# DueShield.net
KiCad netlist of a schematic drawn in EAGLE
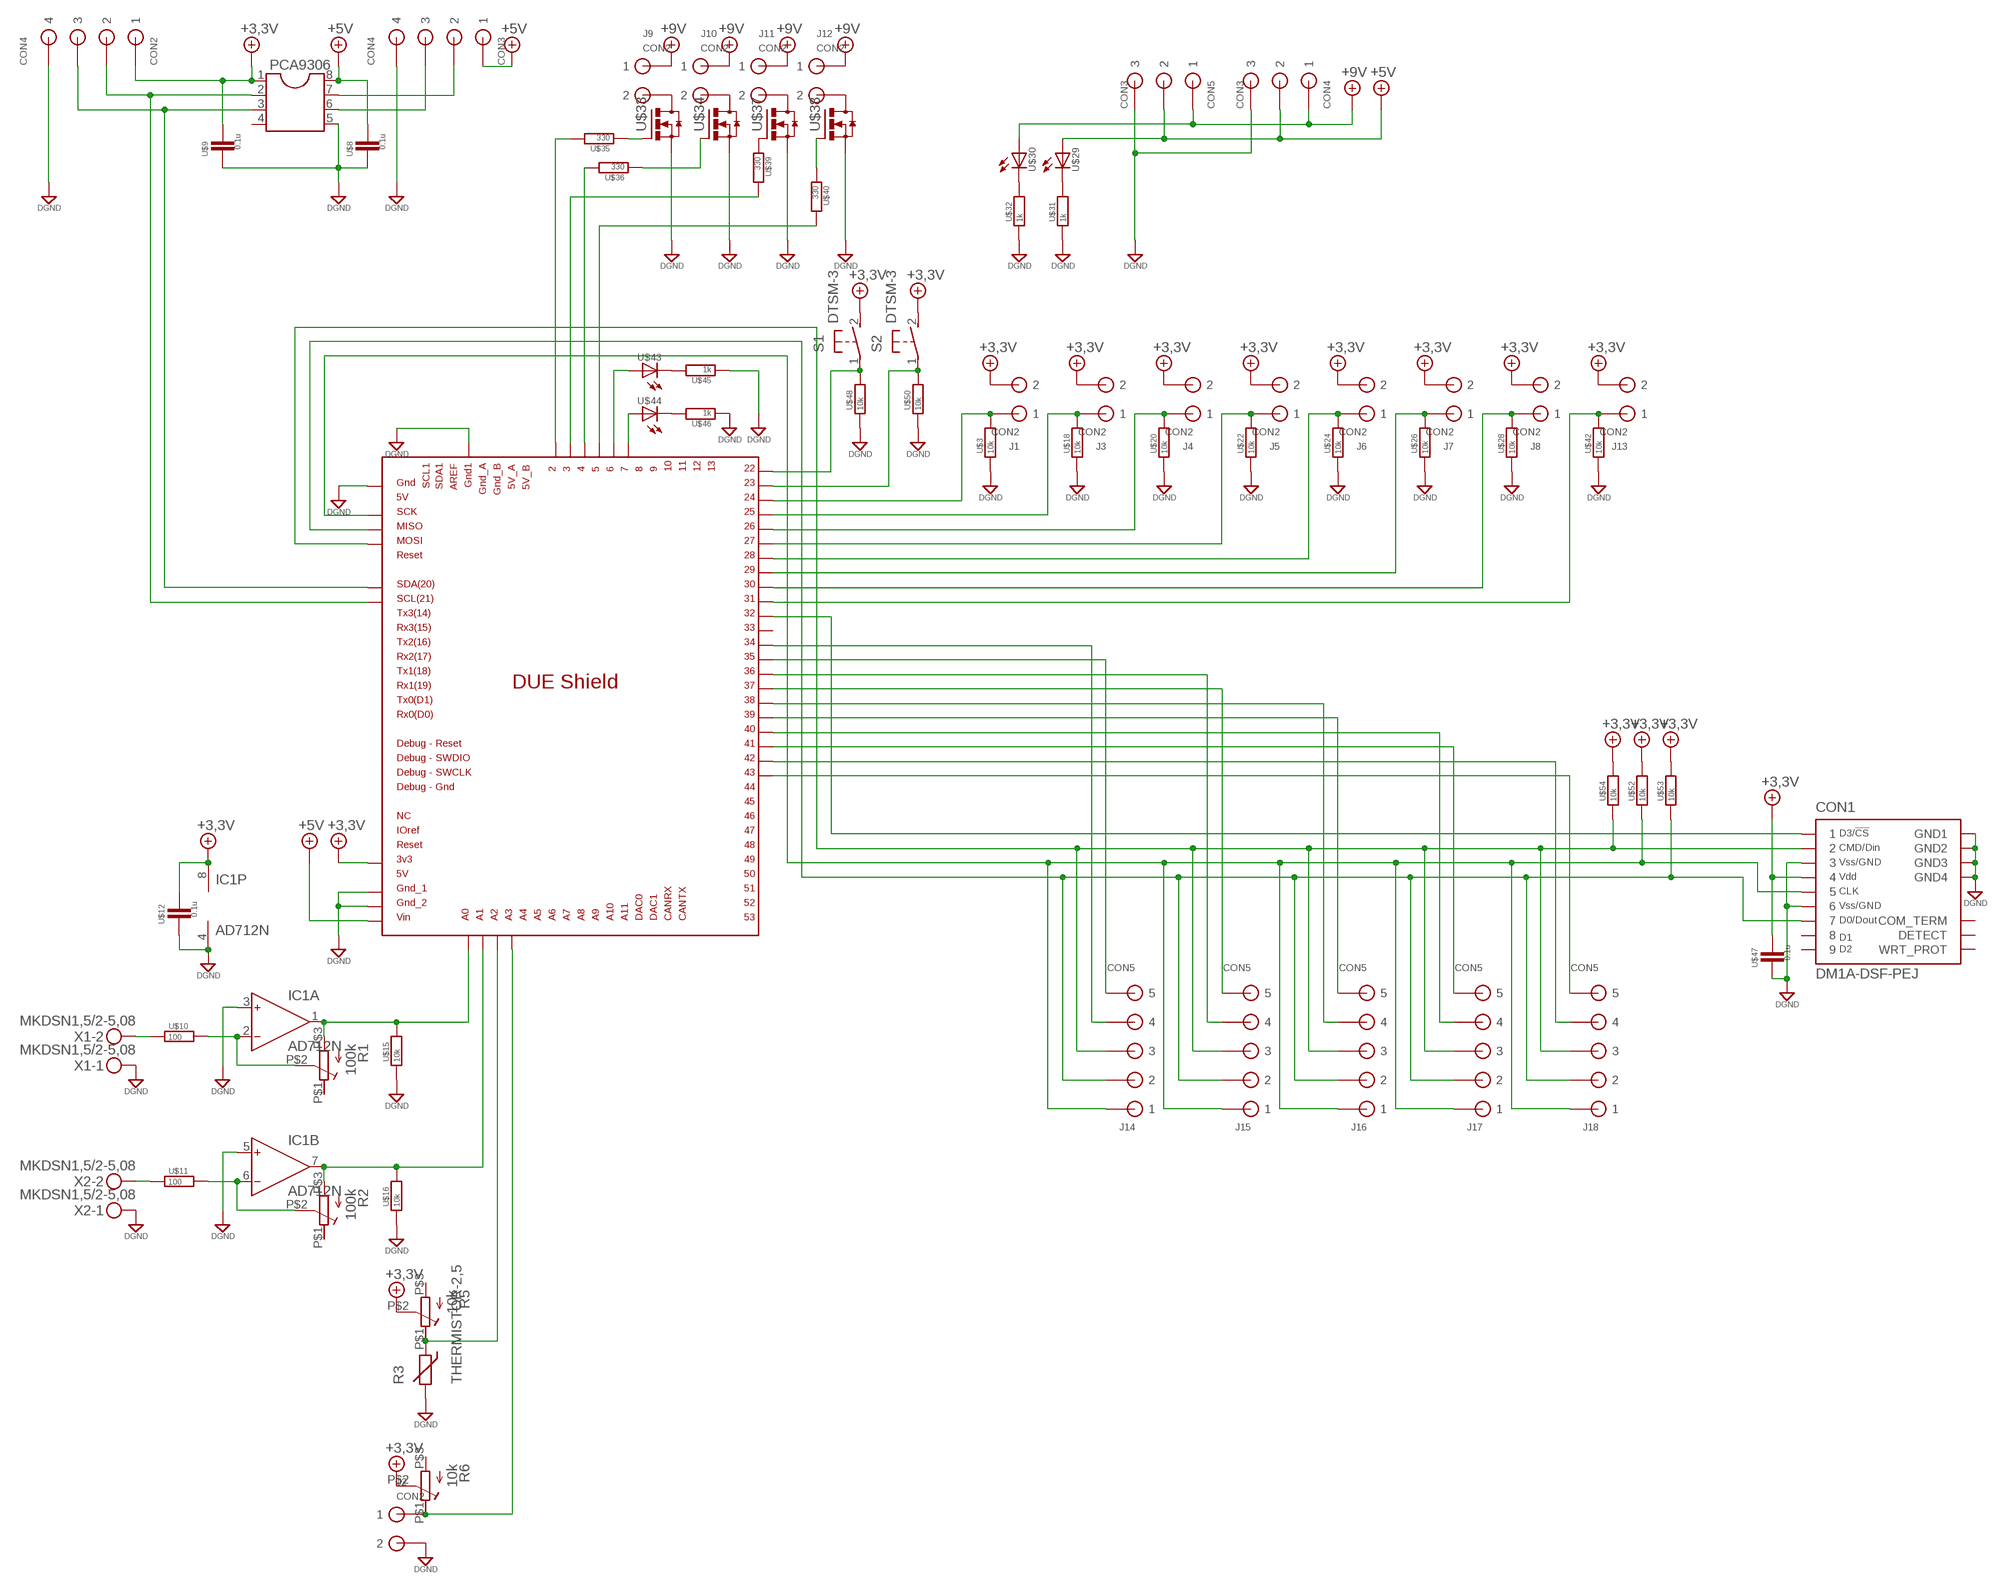
[diagram p0: schematic, sheet 1]

(export (version "E")
  (design (tool "Eeschema 10.0.6"))
  (components
    (comp (ref "CON1")
      (value "DM1A-DSF-PEJ")
      (footprint "eagle-import:DM1A-DSF-PEJ")
      (libsource (lib "eagle-import") (part "DM1A-DSF-PEJ"))
    )
    (comp (ref "CON2")
      (value "CON4")
      (footprint "eagle-import:CON4")
      (libsource (lib "eagle-import") (part "CON4"))
    )
    (comp (ref "CON3")
      (value "CON4")
      (footprint "eagle-import:CON4")
      (libsource (lib "eagle-import") (part "CON4"))
    )
    (comp (ref "CON4")
      (value "CON3")
      (footprint "eagle-import:CON3")
      (libsource (lib "eagle-import") (part "CON3"))
    )
    (comp (ref "CON5")
      (value "CON3")
      (footprint "eagle-import:CON3")
      (libsource (lib "eagle-import") (part "CON3"))
    )
    (comp (ref "IC1")
      (value "AD712N")
      (footprint "eagle-import:DIL08")
      (fields (field (name "MF") "ALTERA CORPORATION") (field (name "MPN") "AD712JNZ"))
      (libsource (lib "eagle-import") (part "AD712N"))
    )
    (comp (ref "J1")
      (value "CON2")
      (footprint "eagle-import:CON2")
      (libsource (lib "eagle-import") (part "CON2"))
    )
    (comp (ref "J2")
      (value "CON2")
      (footprint "eagle-import:CON2")
      (libsource (lib "eagle-import") (part "CON2"))
    )
    (comp (ref "J3")
      (value "CON2")
      (footprint "eagle-import:CON2")
      (libsource (lib "eagle-import") (part "CON2"))
    )
    (comp (ref "J4")
      (value "CON2")
      (footprint "eagle-import:CON2")
      (libsource (lib "eagle-import") (part "CON2"))
    )
    (comp (ref "J5")
      (value "CON2")
      (footprint "eagle-import:CON2")
      (libsource (lib "eagle-import") (part "CON2"))
    )
    (comp (ref "J6")
      (value "CON2")
      (footprint "eagle-import:CON2")
      (libsource (lib "eagle-import") (part "CON2"))
    )
    (comp (ref "J7")
      (value "CON2")
      (footprint "eagle-import:CON2")
      (libsource (lib "eagle-import") (part "CON2"))
    )
    (comp (ref "J8")
      (value "CON2")
      (footprint "eagle-import:CON2")
      (libsource (lib "eagle-import") (part "CON2"))
    )
    (comp (ref "J9")
      (value "CON2")
      (footprint "eagle-import:CON2")
      (libsource (lib "eagle-import") (part "CON2"))
    )
    (comp (ref "J10")
      (value "CON2")
      (footprint "eagle-import:CON2")
      (libsource (lib "eagle-import") (part "CON2"))
    )
    (comp (ref "J11")
      (value "CON2")
      (footprint "eagle-import:CON2")
      (libsource (lib "eagle-import") (part "CON2"))
    )
    (comp (ref "J12")
      (value "CON2")
      (footprint "eagle-import:CON2")
      (libsource (lib "eagle-import") (part "CON2"))
    )
    (comp (ref "J13")
      (value "CON2")
      (footprint "eagle-import:CON2")
      (libsource (lib "eagle-import") (part "CON2"))
    )
    (comp (ref "J14")
      (value "CON5")
      (footprint "eagle-import:CON5")
      (libsource (lib "eagle-import") (part "CON5"))
    )
    (comp (ref "J15")
      (value "CON5")
      (footprint "eagle-import:CON5")
      (libsource (lib "eagle-import") (part "CON5"))
    )
    (comp (ref "J16")
      (value "CON5")
      (footprint "eagle-import:CON5")
      (libsource (lib "eagle-import") (part "CON5"))
    )
    (comp (ref "J17")
      (value "CON5")
      (footprint "eagle-import:CON5")
      (libsource (lib "eagle-import") (part "CON5"))
    )
    (comp (ref "J18")
      (value "CON5")
      (footprint "eagle-import:CON5")
      (libsource (lib "eagle-import") (part "CON5"))
    )
    (comp (ref "PCA9306")
      (value "DIL8")
      (footprint "eagle-import:DIL08")
      (libsource (lib "eagle-import") (part "DIL8"))
    )
    (comp (ref "R1")
      (value "100k")
      (footprint "eagle-import:GF063PB")
      (libsource (lib "eagle-import") (part "抵抗(可変)"))
    )
    (comp (ref "R2")
      (value "100k")
      (footprint "eagle-import:GF063PB")
      (libsource (lib "eagle-import") (part "抵抗(可変)"))
    )
    (comp (ref "R3")
      (value "THERMISTOR-2,5")
      (footprint "eagle-import:RS-2,5")
      (libsource (lib "eagle-import") (part "THERMISTOR-2,5"))
    )
    (comp (ref "R5")
      (value "10k")
      (footprint "eagle-import:GF063PB")
      (libsource (lib "eagle-import") (part "抵抗(可変)"))
    )
    (comp (ref "R6")
      (value "10k")
      (footprint "eagle-import:GF063PB")
      (libsource (lib "eagle-import") (part "抵抗(可変)"))
    )
    (comp (ref "S1")
      (value "DTSM-3")
      (footprint "eagle-import:DTSM-3")
      (libsource (lib "eagle-import") (part "DTSM-3"))
    )
    (comp (ref "S2")
      (value "DTSM-3")
      (footprint "eagle-import:DTSM-3")
      (libsource (lib "eagle-import") (part "DTSM-3"))
    )
    (comp (ref "U$1")
      (value "DUE(3DPRINTER)")
      (footprint "eagle-import:DUE(3DPRITNER)")
      (libsource (lib "eagle-import") (part "DUE(3DPRINTER)"))
    )
    (comp (ref "U$3")
      (value "10k")
      (footprint "eagle-import:0805")
      (libsource (lib "eagle-import") (part "抵抗0805"))
    )
    (comp (ref "U$8")
      (value "0.1u")
      (footprint "eagle-import:0805")
      (libsource (lib "eagle-import") (part "コンデンサ0805"))
    )
    (comp (ref "U$9")
      (value "0.1u")
      (footprint "eagle-import:0805")
      (libsource (lib "eagle-import") (part "コンデンサ0805"))
    )
    (comp (ref "U$10")
      (value "100")
      (footprint "eagle-import:0805")
      (libsource (lib "eagle-import") (part "抵抗0805"))
    )
    (comp (ref "U$11")
      (value "100")
      (footprint "eagle-import:0805")
      (libsource (lib "eagle-import") (part "抵抗0805"))
    )
    (comp (ref "U$12")
      (value "0.1u")
      (footprint "eagle-import:0805")
      (libsource (lib "eagle-import") (part "コンデンサ0805"))
    )
    (comp (ref "U$15")
      (value "10k")
      (footprint "eagle-import:0805")
      (libsource (lib "eagle-import") (part "抵抗0805"))
    )
    (comp (ref "U$16")
      (value "10k")
      (footprint "eagle-import:0805")
      (libsource (lib "eagle-import") (part "抵抗0805"))
    )
    (comp (ref "U$18")
      (value "10k")
      (footprint "eagle-import:0805")
      (libsource (lib "eagle-import") (part "抵抗0805"))
    )
    (comp (ref "U$20")
      (value "10k")
      (footprint "eagle-import:0805")
      (libsource (lib "eagle-import") (part "抵抗0805"))
    )
    (comp (ref "U$22")
      (value "10k")
      (footprint "eagle-import:0805")
      (libsource (lib "eagle-import") (part "抵抗0805"))
    )
    (comp (ref "U$24")
      (value "10k")
      (footprint "eagle-import:0805")
      (libsource (lib "eagle-import") (part "抵抗0805"))
    )
    (comp (ref "U$26")
      (value "10k")
      (footprint "eagle-import:0805")
      (libsource (lib "eagle-import") (part "抵抗0805"))
    )
    (comp (ref "U$28")
      (value "10k")
      (footprint "eagle-import:0805")
      (libsource (lib "eagle-import") (part "抵抗0805"))
    )
    (comp (ref "U$29")
      (value "LED(砲弾型)3")
      (footprint "eagle-import:LED3MM")
      (libsource (lib "eagle-import") (part "LED(砲弾型)3"))
    )
    (comp (ref "U$30")
      (value "LED(砲弾型)3")
      (footprint "eagle-import:LED3MM")
      (libsource (lib "eagle-import") (part "LED(砲弾型)3"))
    )
    (comp (ref "U$31")
      (value "1k")
      (footprint "eagle-import:0805")
      (libsource (lib "eagle-import") (part "抵抗0805"))
    )
    (comp (ref "U$32")
      (value "1k")
      (footprint "eagle-import:0805")
      (libsource (lib "eagle-import") (part "抵抗0805"))
    )
    (comp (ref "U$33")
      (value "TO-252(MOS-FET_N)")
      (footprint "eagle-import:TO-252")
      (libsource (lib "eagle-import") (part "TO-252(MOS-FET_N)"))
    )
    (comp (ref "U$34")
      (value "TO-252(MOS-FET_N)")
      (footprint "eagle-import:TO-252")
      (libsource (lib "eagle-import") (part "TO-252(MOS-FET_N)"))
    )
    (comp (ref "U$35")
      (value "330")
      (footprint "eagle-import:0805")
      (libsource (lib "eagle-import") (part "抵抗0805"))
    )
    (comp (ref "U$36")
      (value "330")
      (footprint "eagle-import:0805")
      (libsource (lib "eagle-import") (part "抵抗0805"))
    )
    (comp (ref "U$37")
      (value "TO-252(MOS-FET_N)")
      (footprint "eagle-import:TO-252")
      (libsource (lib "eagle-import") (part "TO-252(MOS-FET_N)"))
    )
    (comp (ref "U$38")
      (value "TO-252(MOS-FET_N)")
      (footprint "eagle-import:TO-252")
      (libsource (lib "eagle-import") (part "TO-252(MOS-FET_N)"))
    )
    (comp (ref "U$39")
      (value "330")
      (footprint "eagle-import:0805")
      (libsource (lib "eagle-import") (part "抵抗0805"))
    )
    (comp (ref "U$40")
      (value "330")
      (footprint "eagle-import:0805")
      (libsource (lib "eagle-import") (part "抵抗0805"))
    )
    (comp (ref "U$42")
      (value "10k")
      (footprint "eagle-import:0805")
      (libsource (lib "eagle-import") (part "抵抗0805"))
    )
    (comp (ref "U$43")
      (value "LED(砲弾型)3")
      (footprint "eagle-import:LED3MM")
      (libsource (lib "eagle-import") (part "LED(砲弾型)3"))
    )
    (comp (ref "U$44")
      (value "LED(砲弾型)3")
      (footprint "eagle-import:LED3MM")
      (libsource (lib "eagle-import") (part "LED(砲弾型)3"))
    )
    (comp (ref "U$45")
      (value "1k")
      (footprint "eagle-import:0805")
      (libsource (lib "eagle-import") (part "抵抗0805"))
    )
    (comp (ref "U$46")
      (value "1k")
      (footprint "eagle-import:0805")
      (libsource (lib "eagle-import") (part "抵抗0805"))
    )
    (comp (ref "U$47")
      (value "0.1u")
      (footprint "eagle-import:0805")
      (libsource (lib "eagle-import") (part "コンデンサ0805"))
    )
    (comp (ref "U$48")
      (value "10k")
      (footprint "eagle-import:0805")
      (libsource (lib "eagle-import") (part "抵抗0805"))
    )
    (comp (ref "U$50")
      (value "10k")
      (footprint "eagle-import:0805")
      (libsource (lib "eagle-import") (part "抵抗0805"))
    )
    (comp (ref "U$52")
      (value "10k")
      (footprint "eagle-import:0805")
      (libsource (lib "eagle-import") (part "抵抗0805"))
    )
    (comp (ref "U$53")
      (value "10k")
      (footprint "eagle-import:0805")
      (libsource (lib "eagle-import") (part "抵抗0805"))
    )
    (comp (ref "U$54")
      (value "10k")
      (footprint "eagle-import:0805")
      (libsource (lib "eagle-import") (part "抵抗0805"))
    )
    (comp (ref "X1")
      (value "MKDSN1,5/2-5,08")
      (footprint "eagle-import:MKDSN1,5_2-5,08")
      (libsource (lib "eagle-import") (part "MKDSN1,5/2-5,08"))
    )
    (comp (ref "X2")
      (value "MKDSN1,5/2-5,08")
      (footprint "eagle-import:MKDSN1,5_2-5,08")
      (libsource (lib "eagle-import") (part "MKDSN1,5/2-5,08"))
    )
  )
  (nets
    (net (code "1") (name "+3.3V") (class "Default")
      (node (ref "CON1") (pin "4") (pinfunction "4_4") (pintype "power_in"))
      (node (ref "CON2") (pin "P$1") (pinfunction "1_P$1") (pintype "bidirectional"))
      (node (ref "IC1") (pin "8") (pinfunction "V+_8") (pintype "power_in"))
      (node (ref "J1") (pin "P$2") (pinfunction "2_P$2") (pintype "bidirectional"))
      (node (ref "J13") (pin "P$2") (pinfunction "2_P$2") (pintype "bidirectional"))
      (node (ref "J3") (pin "P$2") (pinfunction "2_P$2") (pintype "bidirectional"))
      (node (ref "J4") (pin "P$2") (pinfunction "2_P$2") (pintype "bidirectional"))
      (node (ref "J5") (pin "P$2") (pinfunction "2_P$2") (pintype "bidirectional"))
      (node (ref "J6") (pin "P$2") (pinfunction "2_P$2") (pintype "bidirectional"))
      (node (ref "J7") (pin "P$2") (pinfunction "2_P$2") (pintype "bidirectional"))
      (node (ref "J8") (pin "P$2") (pinfunction "2_P$2") (pintype "bidirectional"))
      (node (ref "PCA9306") (pin "1") (pinfunction "1_1") (pintype "passive"))
      (node (ref "R5") (pin "P$2") (pinfunction "S_P$2") (pintype "passive"))
      (node (ref "R6") (pin "P$2") (pinfunction "S_P$2") (pintype "passive"))
      (node (ref "S1") (pin "2") (pinfunction "2_2") (pintype "passive"))
      (node (ref "S2") (pin "2") (pinfunction "2_2") (pintype "passive"))
      (node (ref "U$1") (pin "3V3") (pinfunction "3V3_3V3") (pintype "bidirectional"))
      (node (ref "U$12") (pin "1") (pinfunction "1_1") (pintype "passive"))
      (node (ref "U$47") (pin "1") (pinfunction "1_1") (pintype "passive"))
      (node (ref "U$52") (pin "2") (pinfunction "2_2") (pintype "passive"))
      (node (ref "U$53") (pin "2") (pinfunction "2_2") (pintype "passive"))
      (node (ref "U$54") (pin "2") (pinfunction "2_2") (pintype "passive"))
      (node (ref "U$9") (pin "1") (pinfunction "1_1") (pintype "passive"))
    )
    (net (code "2") (name "+5V") (class "Default")
      (node (ref "CON3") (pin "P$1") (pinfunction "1_P$1") (pintype "bidirectional"))
      (node (ref "CON4") (pin "P$2") (pinfunction "2_P$2") (pintype "bidirectional"))
      (node (ref "CON5") (pin "P$2") (pinfunction "2_P$2") (pintype "bidirectional"))
      (node (ref "PCA9306") (pin "8") (pinfunction "8_8") (pintype "passive"))
      (node (ref "U$1") (pin "VIN") (pinfunction "VIN_VIN") (pintype "bidirectional"))
      (node (ref "U$29") (pin "A") (pinfunction "A_A") (pintype "passive"))
      (node (ref "U$8") (pin "1") (pinfunction "1_1") (pintype "passive"))
    )
    (net (code "3") (name "+9V") (class "Default")
      (node (ref "CON4") (pin "P$1") (pinfunction "1_P$1") (pintype "bidirectional"))
      (node (ref "CON5") (pin "P$1") (pinfunction "1_P$1") (pintype "bidirectional"))
      (node (ref "J10") (pin "P$1") (pinfunction "1_P$1") (pintype "bidirectional"))
      (node (ref "J11") (pin "P$1") (pinfunction "1_P$1") (pintype "bidirectional"))
      (node (ref "J12") (pin "P$1") (pinfunction "1_P$1") (pintype "bidirectional"))
      (node (ref "J9") (pin "P$1") (pinfunction "1_P$1") (pintype "bidirectional"))
      (node (ref "U$30") (pin "A") (pinfunction "A_A") (pintype "passive"))
    )
    (net (code "4") (name "DGND") (class "Default")
      (node (ref "CON1") (pin "3") (pinfunction "3_3") (pintype "power_in"))
      (node (ref "CON1") (pin "6") (pinfunction "6_6") (pintype "power_in"))
      (node (ref "CON1") (pin "GND1") (pinfunction "GND1_GND1") (pintype "power_in"))
      (node (ref "CON1") (pin "GND2") (pinfunction "GND2_GND2") (pintype "power_in"))
      (node (ref "CON1") (pin "GND3") (pinfunction "GND3_GND3") (pintype "power_in"))
      (node (ref "CON1") (pin "GND4") (pinfunction "GND4_GND4") (pintype "power_in"))
      (node (ref "CON2") (pin "P$4") (pinfunction "4_P$4") (pintype "bidirectional"))
      (node (ref "CON3") (pin "P$4") (pinfunction "4_P$4") (pintype "bidirectional"))
      (node (ref "CON4") (pin "P$3") (pinfunction "3_P$3") (pintype "bidirectional"))
      (node (ref "CON5") (pin "P$3") (pinfunction "3_P$3") (pintype "bidirectional"))
      (node (ref "IC1") (pin "3") (pinfunction "IN+_3") (pintype "input"))
      (node (ref "IC1") (pin "4") (pinfunction "V-_4") (pintype "power_in"))
      (node (ref "IC1") (pin "5") (pinfunction "IN+_5") (pintype "input"))
      (node (ref "J2") (pin "P$2") (pinfunction "2_P$2") (pintype "bidirectional"))
      (node (ref "PCA9306") (pin "5") (pinfunction "5_5") (pintype "passive"))
      (node (ref "R3") (pin "2") (pinfunction "2_2") (pintype "passive"))
      (node (ref "U$1") (pin "5V_ICSP") (pinfunction "5V_ICSP_5V_ICSP") (pintype "bidirectional"))
      (node (ref "U$1") (pin "GND1") (pinfunction "GND1_GND1") (pintype "bidirectional"))
      (node (ref "U$1") (pin "GND_1") (pinfunction "GND_1_GND_1") (pintype "bidirectional"))
      (node (ref "U$1") (pin "GND_2") (pinfunction "GND_2_GND_2") (pintype "bidirectional"))
      (node (ref "U$12") (pin "2") (pinfunction "2_2") (pintype "passive"))
      (node (ref "U$15") (pin "1") (pinfunction "1_1") (pintype "passive"))
      (node (ref "U$16") (pin "1") (pinfunction "1_1") (pintype "passive"))
      (node (ref "U$18") (pin "1") (pinfunction "1_1") (pintype "passive"))
      (node (ref "U$20") (pin "1") (pinfunction "1_1") (pintype "passive"))
      (node (ref "U$22") (pin "1") (pinfunction "1_1") (pintype "passive"))
      (node (ref "U$24") (pin "1") (pinfunction "1_1") (pintype "passive"))
      (node (ref "U$26") (pin "1") (pinfunction "1_1") (pintype "passive"))
      (node (ref "U$28") (pin "1") (pinfunction "1_1") (pintype "passive"))
      (node (ref "U$3") (pin "1") (pinfunction "1_1") (pintype "passive"))
      (node (ref "U$31") (pin "1") (pinfunction "1_1") (pintype "passive"))
      (node (ref "U$32") (pin "1") (pinfunction "1_1") (pintype "passive"))
      (node (ref "U$33") (pin "2") (pinfunction "S_2") (pintype "passive"))
      (node (ref "U$34") (pin "2") (pinfunction "S_2") (pintype "passive"))
      (node (ref "U$37") (pin "2") (pinfunction "S_2") (pintype "passive"))
      (node (ref "U$38") (pin "2") (pinfunction "S_2") (pintype "passive"))
      (node (ref "U$42") (pin "1") (pinfunction "1_1") (pintype "passive"))
      (node (ref "U$45") (pin "1") (pinfunction "1_1") (pintype "passive"))
      (node (ref "U$46") (pin "1") (pinfunction "1_1") (pintype "passive"))
      (node (ref "U$47") (pin "2") (pinfunction "2_2") (pintype "passive"))
      (node (ref "U$48") (pin "1") (pinfunction "1_1") (pintype "passive"))
      (node (ref "U$50") (pin "1") (pinfunction "1_1") (pintype "passive"))
      (node (ref "U$8") (pin "2") (pinfunction "2_2") (pintype "passive"))
      (node (ref "U$9") (pin "2") (pinfunction "2_2") (pintype "passive"))
      (node (ref "X1") (pin "1") (pinfunction "KL_1") (pintype "passive"))
      (node (ref "X2") (pin "1") (pinfunction "KL_1") (pintype "passive"))
    )
    (net (code "5") (name "Net-(CON1-Pad1)") (class "Default")
      (node (ref "CON1") (pin "1") (pinfunction "1_1") (pintype "bidirectional"))
      (node (ref "U$1") (pin "32") (pinfunction "32_32") (pintype "bidirectional"))
    )
    (net (code "6") (name "Net-(CON2-2)") (class "Default")
      (node (ref "CON2") (pin "P$2") (pinfunction "2_P$2") (pintype "bidirectional"))
      (node (ref "PCA9306") (pin "2") (pinfunction "2_2") (pintype "passive"))
      (node (ref "U$1") (pin "SCL") (pinfunction "SCL_SCL") (pintype "bidirectional"))
    )
    (net (code "7") (name "Net-(CON2-3)") (class "Default")
      (node (ref "CON2") (pin "P$3") (pinfunction "3_P$3") (pintype "bidirectional"))
      (node (ref "PCA9306") (pin "3") (pinfunction "3_3") (pintype "passive"))
      (node (ref "U$1") (pin "SDA") (pinfunction "SDA_SDA") (pintype "bidirectional"))
    )
    (net (code "8") (name "Net-(CON3-2)") (class "Default")
      (node (ref "CON3") (pin "P$2") (pinfunction "2_P$2") (pintype "bidirectional"))
      (node (ref "PCA9306") (pin "7") (pinfunction "7_7") (pintype "passive"))
    )
    (net (code "9") (name "Net-(CON3-3)") (class "Default")
      (node (ref "CON3") (pin "P$3") (pinfunction "3_P$3") (pintype "bidirectional"))
      (node (ref "PCA9306") (pin "6") (pinfunction "6_6") (pintype "passive"))
    )
    (net (code "10") (name "Net-(IC1A-IN-)") (class "Default")
      (node (ref "IC1") (pin "2") (pinfunction "IN-_2") (pintype "input"))
      (node (ref "R1") (pin "P$2") (pinfunction "S_P$2") (pintype "passive"))
      (node (ref "U$10") (pin "2") (pinfunction "2_2") (pintype "passive"))
    )
    (net (code "11") (name "Net-(IC1A-OUT)") (class "Default")
      (node (ref "IC1") (pin "1") (pinfunction "OUT_1") (pintype "output"))
      (node (ref "R1") (pin "P$3") (pinfunction "A_P$3") (pintype "passive"))
      (node (ref "U$1") (pin "A0") (pinfunction "A0_A0") (pintype "bidirectional"))
      (node (ref "U$15") (pin "2") (pinfunction "2_2") (pintype "passive"))
    )
    (net (code "12") (name "Net-(IC1B-IN-)") (class "Default")
      (node (ref "IC1") (pin "6") (pinfunction "IN-_6") (pintype "input"))
      (node (ref "R2") (pin "P$2") (pinfunction "S_P$2") (pintype "passive"))
      (node (ref "U$11") (pin "2") (pinfunction "2_2") (pintype "passive"))
    )
    (net (code "13") (name "Net-(IC1B-OUT)") (class "Default")
      (node (ref "IC1") (pin "7") (pinfunction "OUT_7") (pintype "output"))
      (node (ref "R2") (pin "P$3") (pinfunction "A_P$3") (pintype "passive"))
      (node (ref "U$1") (pin "A1") (pinfunction "A1_A1") (pintype "bidirectional"))
      (node (ref "U$16") (pin "2") (pinfunction "2_2") (pintype "passive"))
    )
    (net (code "14") (name "Net-(J1-1)") (class "Default")
      (node (ref "J1") (pin "P$1") (pinfunction "1_P$1") (pintype "bidirectional"))
      (node (ref "U$1") (pin "24") (pinfunction "24_24") (pintype "bidirectional"))
      (node (ref "U$3") (pin "2") (pinfunction "2_2") (pintype "passive"))
    )
    (net (code "15") (name "Net-(J2-1)") (class "Default")
      (node (ref "J2") (pin "P$1") (pinfunction "1_P$1") (pintype "bidirectional"))
      (node (ref "R6") (pin "P$1") (pinfunction "E_P$1") (pintype "passive"))
      (node (ref "U$1") (pin "A3") (pinfunction "A3_A3") (pintype "bidirectional"))
    )
    (net (code "16") (name "Net-(J3-1)") (class "Default")
      (node (ref "J3") (pin "P$1") (pinfunction "1_P$1") (pintype "bidirectional"))
      (node (ref "U$1") (pin "25") (pinfunction "25_25") (pintype "bidirectional"))
      (node (ref "U$18") (pin "2") (pinfunction "2_2") (pintype "passive"))
    )
    (net (code "17") (name "Net-(J4-1)") (class "Default")
      (node (ref "J4") (pin "P$1") (pinfunction "1_P$1") (pintype "bidirectional"))
      (node (ref "U$1") (pin "26") (pinfunction "26_26") (pintype "bidirectional"))
      (node (ref "U$20") (pin "2") (pinfunction "2_2") (pintype "passive"))
    )
    (net (code "18") (name "Net-(J5-1)") (class "Default")
      (node (ref "J5") (pin "P$1") (pinfunction "1_P$1") (pintype "bidirectional"))
      (node (ref "U$1") (pin "27") (pinfunction "27_27") (pintype "bidirectional"))
      (node (ref "U$22") (pin "2") (pinfunction "2_2") (pintype "passive"))
    )
    (net (code "19") (name "Net-(J6-1)") (class "Default")
      (node (ref "J6") (pin "P$1") (pinfunction "1_P$1") (pintype "bidirectional"))
      (node (ref "U$1") (pin "28") (pinfunction "28_28") (pintype "bidirectional"))
      (node (ref "U$24") (pin "2") (pinfunction "2_2") (pintype "passive"))
    )
    (net (code "20") (name "Net-(J7-1)") (class "Default")
      (node (ref "J7") (pin "P$1") (pinfunction "1_P$1") (pintype "bidirectional"))
      (node (ref "U$1") (pin "29") (pinfunction "29_29") (pintype "bidirectional"))
      (node (ref "U$26") (pin "2") (pinfunction "2_2") (pintype "passive"))
    )
    (net (code "21") (name "Net-(J8-1)") (class "Default")
      (node (ref "J8") (pin "P$1") (pinfunction "1_P$1") (pintype "bidirectional"))
      (node (ref "U$1") (pin "30") (pinfunction "30_30") (pintype "bidirectional"))
      (node (ref "U$28") (pin "2") (pinfunction "2_2") (pintype "passive"))
    )
    (net (code "22") (name "Net-(J9-2)") (class "Default")
      (node (ref "J9") (pin "P$2") (pinfunction "2_P$2") (pintype "bidirectional"))
      (node (ref "U$33") (pin "3") (pinfunction "D_3") (pintype "passive"))
    )
    (net (code "23") (name "Net-(J10-2)") (class "Default")
      (node (ref "J10") (pin "P$2") (pinfunction "2_P$2") (pintype "bidirectional"))
      (node (ref "U$34") (pin "3") (pinfunction "D_3") (pintype "passive"))
    )
    (net (code "24") (name "Net-(J11-2)") (class "Default")
      (node (ref "J11") (pin "P$2") (pinfunction "2_P$2") (pintype "bidirectional"))
      (node (ref "U$37") (pin "3") (pinfunction "D_3") (pintype "passive"))
    )
    (net (code "25") (name "Net-(J12-2)") (class "Default")
      (node (ref "J12") (pin "P$2") (pinfunction "2_P$2") (pintype "bidirectional"))
      (node (ref "U$38") (pin "3") (pinfunction "D_3") (pintype "passive"))
    )
    (net (code "26") (name "Net-(J13-1)") (class "Default")
      (node (ref "J13") (pin "P$1") (pinfunction "1_P$1") (pintype "bidirectional"))
      (node (ref "U$1") (pin "31") (pinfunction "31_31") (pintype "bidirectional"))
      (node (ref "U$42") (pin "2") (pinfunction "2_2") (pintype "passive"))
    )
    (net (code "27") (name "Net-(J14-1)") (class "Default")
      (node (ref "CON1") (pin "5") (pinfunction "5_5") (pintype "input"))
      (node (ref "J14") (pin "P$1") (pinfunction "1_P$1") (pintype "bidirectional"))
      (node (ref "J15") (pin "P$1") (pinfunction "1_P$1") (pintype "bidirectional"))
      (node (ref "J16") (pin "P$1") (pinfunction "1_P$1") (pintype "bidirectional"))
      (node (ref "J17") (pin "P$1") (pinfunction "1_P$1") (pintype "bidirectional"))
      (node (ref "J18") (pin "P$1") (pinfunction "1_P$1") (pintype "bidirectional"))
      (node (ref "U$1") (pin "SCK_ICSP") (pinfunction "SCK_ICSP_SCK_ICSP") (pintype "bidirectional"))
      (node (ref "U$52") (pin "1") (pinfunction "1_1") (pintype "passive"))
    )
    (net (code "28") (name "Net-(J14-2)") (class "Default")
      (node (ref "CON1") (pin "7") (pinfunction "7_7") (pintype "bidirectional"))
      (node (ref "J14") (pin "P$2") (pinfunction "2_P$2") (pintype "bidirectional"))
      (node (ref "J15") (pin "P$2") (pinfunction "2_P$2") (pintype "bidirectional"))
      (node (ref "J16") (pin "P$2") (pinfunction "2_P$2") (pintype "bidirectional"))
      (node (ref "J17") (pin "P$2") (pinfunction "2_P$2") (pintype "bidirectional"))
      (node (ref "J18") (pin "P$2") (pinfunction "2_P$2") (pintype "bidirectional"))
      (node (ref "U$1") (pin "MISO_ICSP") (pinfunction "MISO_ICSP_MISO_ICSP") (pintype "bidirectional"))
      (node (ref "U$53") (pin "1") (pinfunction "1_1") (pintype "passive"))
    )
    (net (code "29") (name "Net-(J14-3)") (class "Default")
      (node (ref "CON1") (pin "2") (pinfunction "2_2") (pintype "input"))
      (node (ref "J14") (pin "P$3") (pinfunction "3_P$3") (pintype "bidirectional"))
      (node (ref "J15") (pin "P$3") (pinfunction "3_P$3") (pintype "bidirectional"))
      (node (ref "J16") (pin "P$3") (pinfunction "3_P$3") (pintype "bidirectional"))
      (node (ref "J17") (pin "P$3") (pinfunction "3_P$3") (pintype "bidirectional"))
      (node (ref "J18") (pin "P$3") (pinfunction "3_P$3") (pintype "bidirectional"))
      (node (ref "U$1") (pin "MOSI_ICSP") (pinfunction "MOSI_ICSP_MOSI_ICSP") (pintype "bidirectional"))
      (node (ref "U$54") (pin "1") (pinfunction "1_1") (pintype "passive"))
    )
    (net (code "30") (name "Net-(J14-4)") (class "Default")
      (node (ref "J14") (pin "P$4") (pinfunction "4_P$4") (pintype "bidirectional"))
      (node (ref "U$1") (pin "34") (pinfunction "34_34") (pintype "bidirectional"))
    )
    (net (code "31") (name "Net-(J14-5)") (class "Default")
      (node (ref "J14") (pin "P$5") (pinfunction "5_P$5") (pintype "bidirectional"))
      (node (ref "U$1") (pin "35") (pinfunction "35_35") (pintype "bidirectional"))
    )
    (net (code "32") (name "Net-(J15-4)") (class "Default")
      (node (ref "J15") (pin "P$4") (pinfunction "4_P$4") (pintype "bidirectional"))
      (node (ref "U$1") (pin "36") (pinfunction "36_36") (pintype "bidirectional"))
    )
    (net (code "33") (name "Net-(J15-5)") (class "Default")
      (node (ref "J15") (pin "P$5") (pinfunction "5_P$5") (pintype "bidirectional"))
      (node (ref "U$1") (pin "37") (pinfunction "37_37") (pintype "bidirectional"))
    )
    (net (code "34") (name "Net-(J16-4)") (class "Default")
      (node (ref "J16") (pin "P$4") (pinfunction "4_P$4") (pintype "bidirectional"))
      (node (ref "U$1") (pin "38") (pinfunction "38_38") (pintype "bidirectional"))
    )
    (net (code "35") (name "Net-(J16-5)") (class "Default")
      (node (ref "J16") (pin "P$5") (pinfunction "5_P$5") (pintype "bidirectional"))
      (node (ref "U$1") (pin "39") (pinfunction "39_39") (pintype "bidirectional"))
    )
    (net (code "36") (name "Net-(J17-4)") (class "Default")
      (node (ref "J17") (pin "P$4") (pinfunction "4_P$4") (pintype "bidirectional"))
      (node (ref "U$1") (pin "40") (pinfunction "40_40") (pintype "bidirectional"))
    )
    (net (code "37") (name "Net-(J17-5)") (class "Default")
      (node (ref "J17") (pin "P$5") (pinfunction "5_P$5") (pintype "bidirectional"))
      (node (ref "U$1") (pin "41") (pinfunction "41_41") (pintype "bidirectional"))
    )
    (net (code "38") (name "Net-(J18-4)") (class "Default")
      (node (ref "J18") (pin "P$4") (pinfunction "4_P$4") (pintype "bidirectional"))
      (node (ref "U$1") (pin "42") (pinfunction "42_42") (pintype "bidirectional"))
    )
    (net (code "39") (name "Net-(J18-5)") (class "Default")
      (node (ref "J18") (pin "P$5") (pinfunction "5_P$5") (pintype "bidirectional"))
      (node (ref "U$1") (pin "43") (pinfunction "43_43") (pintype "bidirectional"))
    )
    (net (code "40") (name "Net-(R5-E)") (class "Default")
      (node (ref "R3") (pin "1") (pinfunction "1_1") (pintype "passive"))
      (node (ref "R5") (pin "P$1") (pinfunction "E_P$1") (pintype "passive"))
      (node (ref "U$1") (pin "A2") (pinfunction "A2_A2") (pintype "bidirectional"))
    )
    (net (code "41") (name "Net-(S1-Pad1)") (class "Default")
      (node (ref "S1") (pin "1") (pinfunction "1_1") (pintype "passive"))
      (node (ref "U$1") (pin "22") (pinfunction "22_22") (pintype "bidirectional"))
      (node (ref "U$48") (pin "2") (pinfunction "2_2") (pintype "passive"))
    )
    (net (code "42") (name "Net-(S2-Pad1)") (class "Default")
      (node (ref "S2") (pin "1") (pinfunction "1_1") (pintype "passive"))
      (node (ref "U$1") (pin "23") (pinfunction "23_23") (pintype "bidirectional"))
      (node (ref "U$50") (pin "2") (pinfunction "2_2") (pintype "passive"))
    )
    (net (code "43") (name "Net-(U$1-Pad2)") (class "Default")
      (node (ref "U$1") (pin "2") (pinfunction "2_2") (pintype "bidirectional"))
      (node (ref "U$35") (pin "2") (pinfunction "2_2") (pintype "passive"))
    )
    (net (code "44") (name "Net-(U$1-Pad3)") (class "Default")
      (node (ref "U$1") (pin "3") (pinfunction "3_3") (pintype "bidirectional"))
      (node (ref "U$39") (pin "2") (pinfunction "2_2") (pintype "passive"))
    )
    (net (code "45") (name "Net-(U$1-Pad4)") (class "Default")
      (node (ref "U$1") (pin "4") (pinfunction "4_4") (pintype "bidirectional"))
      (node (ref "U$36") (pin "2") (pinfunction "2_2") (pintype "passive"))
    )
    (net (code "46") (name "Net-(U$1-Pad5)") (class "Default")
      (node (ref "U$1") (pin "5") (pinfunction "5_5") (pintype "bidirectional"))
      (node (ref "U$40") (pin "2") (pinfunction "2_2") (pintype "passive"))
    )
    (net (code "47") (name "Net-(U$1-Pad6)") (class "Default")
      (node (ref "U$1") (pin "6") (pinfunction "6_6") (pintype "bidirectional"))
      (node (ref "U$43") (pin "A") (pinfunction "A_A") (pintype "passive"))
    )
    (net (code "48") (name "Net-(U$1-Pad7)") (class "Default")
      (node (ref "U$1") (pin "7") (pinfunction "7_7") (pintype "bidirectional"))
      (node (ref "U$44") (pin "A") (pinfunction "A_A") (pintype "passive"))
    )
    (net (code "49") (name "Net-(U$29-PadK)") (class "Default")
      (node (ref "U$29") (pin "K") (pinfunction "K_K") (pintype "passive"))
      (node (ref "U$31") (pin "2") (pinfunction "2_2") (pintype "passive"))
    )
    (net (code "50") (name "Net-(U$30-PadK)") (class "Default")
      (node (ref "U$30") (pin "K") (pinfunction "K_K") (pintype "passive"))
      (node (ref "U$32") (pin "2") (pinfunction "2_2") (pintype "passive"))
    )
    (net (code "51") (name "Net-(U$33-G)") (class "Default")
      (node (ref "U$33") (pin "1") (pinfunction "G_1") (pintype "passive"))
      (node (ref "U$35") (pin "1") (pinfunction "1_1") (pintype "passive"))
    )
    (net (code "52") (name "Net-(U$34-G)") (class "Default")
      (node (ref "U$34") (pin "1") (pinfunction "G_1") (pintype "passive"))
      (node (ref "U$36") (pin "1") (pinfunction "1_1") (pintype "passive"))
    )
    (net (code "53") (name "Net-(U$37-G)") (class "Default")
      (node (ref "U$37") (pin "1") (pinfunction "G_1") (pintype "passive"))
      (node (ref "U$39") (pin "1") (pinfunction "1_1") (pintype "passive"))
    )
    (net (code "54") (name "Net-(U$38-G)") (class "Default")
      (node (ref "U$38") (pin "1") (pinfunction "G_1") (pintype "passive"))
      (node (ref "U$40") (pin "1") (pinfunction "1_1") (pintype "passive"))
    )
    (net (code "55") (name "Net-(U$43-PadK)") (class "Default")
      (node (ref "U$43") (pin "K") (pinfunction "K_K") (pintype "passive"))
      (node (ref "U$45") (pin "2") (pinfunction "2_2") (pintype "passive"))
    )
    (net (code "56") (name "Net-(U$44-PadK)") (class "Default")
      (node (ref "U$44") (pin "K") (pinfunction "K_K") (pintype "passive"))
      (node (ref "U$46") (pin "2") (pinfunction "2_2") (pintype "passive"))
    )
    (net (code "57") (name "Net-(X1B-KL)") (class "Default")
      (node (ref "U$10") (pin "1") (pinfunction "1_1") (pintype "passive"))
      (node (ref "X1") (pin "2") (pinfunction "KL_2") (pintype "passive"))
    )
    (net (code "58") (name "Net-(X2B-KL)") (class "Default")
      (node (ref "U$11") (pin "1") (pinfunction "1_1") (pintype "passive"))
      (node (ref "X2") (pin "2") (pinfunction "KL_2") (pintype "passive"))
    )
    (net (code "59") (name "unconnected-(CON1-Pad8)") (class "Default")
      (node (ref "CON1") (pin "8") (pinfunction "8_8") (pintype "bidirectional"))
    )
    (net (code "60") (name "unconnected-(CON1-Pad9)") (class "Default")
      (node (ref "CON1") (pin "9") (pinfunction "9_9") (pintype "bidirectional"))
    )
    (net (code "61") (name "unconnected-(CON1-PadCOM_TERM)") (class "Default")
      (node (ref "CON1") (pin "COM_TERM") (pinfunction "COM_TERM_COM_TERM") (pintype "output"))
    )
    (net (code "62") (name "unconnected-(CON1-PadDETECT)") (class "Default")
      (node (ref "CON1") (pin "DETECT") (pinfunction "DETECT_DETECT") (pintype "output"))
    )
    (net (code "63") (name "unconnected-(CON1-PadWRT_PROT)") (class "Default")
      (node (ref "CON1") (pin "WRT_PROT") (pinfunction "WRT_PROT_WRT_PROT") (pintype "output"))
    )
    (net (code "64") (name "unconnected-(PCA9306-Pad4)") (class "Default")
      (node (ref "PCA9306") (pin "4") (pinfunction "4_4") (pintype "passive"))
    )
    (net (code "65") (name "unconnected-(R1-E-PadP$1)") (class "Default")
      (node (ref "R1") (pin "P$1") (pinfunction "E_P$1") (pintype "passive"))
    )
    (net (code "66") (name "unconnected-(R2-E-PadP$1)") (class "Default")
      (node (ref "R2") (pin "P$1") (pinfunction "E_P$1") (pintype "passive"))
    )
    (net (code "67") (name "unconnected-(R5-A-PadP$3)") (class "Default")
      (node (ref "R5") (pin "P$3") (pinfunction "A_P$3") (pintype "passive"))
    )
    (net (code "68") (name "unconnected-(R6-A-PadP$3)") (class "Default")
      (node (ref "R6") (pin "P$3") (pinfunction "A_P$3") (pintype "passive"))
    )
    (net (code "69") (name "unconnected-(U$1-Pad33)") (class "Default")
      (node (ref "U$1") (pin "33") (pinfunction "33_33") (pintype "bidirectional"))
    )
  )
)
